# PTC_Thermistor_470R_VDiv.net
KiCad netlist of a schematic drawn in Altium Designer
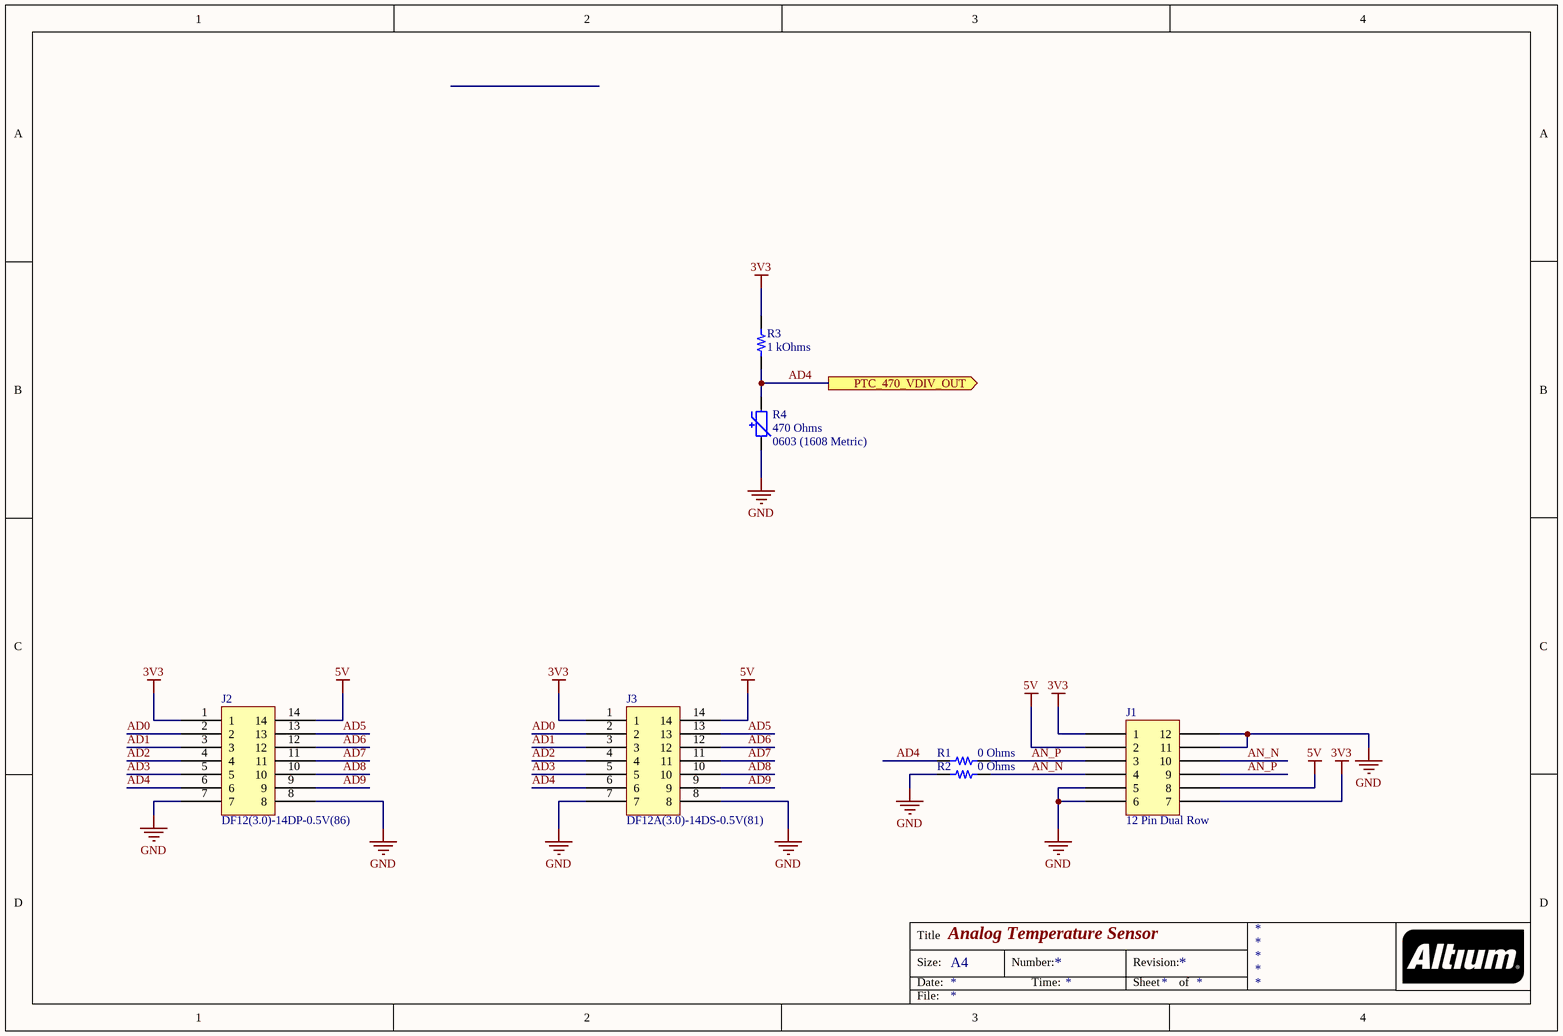
[diagram p0: PTC Thermistor 470R VDiv.SchDoc]

(export (version "E")
  (design (tool "Eeschema 10.0.6"))
  (components
    (comp (ref "J1")
      (value "12 Pin Dual Row")
      (footprint "TE 5650118-3 Card Edge")
      (libsource (lib "CelestialUseful") (part "12 Pin Dual Row"))
    )
    (comp (ref "J2")
      (value "DF12(3.0)-14DP-0.5V(86)")
      (footprint "HIROSE DF12 3.0-14DP-0.5V 86")
      (description "CONN HDR 14POS SMD GOLD")
      (fields (field (name "MANUFACTURER") "Hirose Electric Co Ltd"))
      (libsource (lib "altiumlibrary.com") (part "14 Pin Dual Row"))
    )
    (comp (ref "J3")
      (value "DF12A(3.0)-14DS-0.5V(81)")
      (footprint "HIROSE DF12A 3.0-14DS-0.5V 81")
      (description "CONN RCPT 14POS SMD GOLD")
      (fields (field (name "MANUFACTURER") "Hirose Electric Co Ltd"))
      (libsource (lib "altiumlibrary.com") (part "14 Pin Dual Row"))
    )
    (comp (ref "R1")
      (value "0 Ohms")
      (footprint "RES 0603_1608")
      (description "RES SMD 0 OHM JUMPER 1/10W 0603")
      (fields
        (field (name "PART NUMBER") "ERJ-3GEY0R00V")
        (field (name "MANUFACTURER") "Panasonic Electronic Components")
      )
      (libsource (lib "altiumlibrary.com") (part "Resistor"))
    )
    (comp (ref "R2")
      (value "0 Ohms")
      (footprint "RES 0603_1608")
      (description "RES SMD 0 OHM JUMPER 1/10W 0603")
      (fields
        (field (name "PART NUMBER") "ERJ-3GEY0R00V")
        (field (name "MANUFACTURER") "Panasonic Electronic Components")
      )
      (libsource (lib "altiumlibrary.com") (part "Resistor"))
    )
    (comp (ref "R3")
      (value "1 kOhms")
      (footprint "RES 0603_1608")
      (description "RES SMD 1K OHM 1% 1/10W 0603")
      (fields
        (field (name "PART NUMBER") "ERJ-3EKF1001V")
        (field (name "MANUFACTURER") "Panasonic Electronic Components")
      )
      (libsource (lib "altiumlibrary.com") (part "Resistor"))
    )
    (comp (ref "R4")
      (value "470 Ohms")
      (footprint "PTC 0603_1608")
      (description "THERMISTOR PTC 470 OHM 50% 0603")
      (fields
        (field (name "PART NUMBER") "PRF18BB471QB5RB")
        (field (name "MANUFACTURER") "Murata Electronics")
        (field (name "PACKAGE / CASE") "0603 (1608 Metric)")
      )
      (libsource (lib "altiumlibrary.com") (part "Thermistor PTC"))
    )
  )
  (nets
    (net (code "1") (name "/AD0") (class "Default")
      (node (ref "J2") (pin "2") (pinfunction "2_2") (pintype "passive"))
      (node (ref "J3") (pin "2") (pinfunction "2_2") (pintype "passive"))
    )
    (net (code "2") (name "/AD1") (class "Default")
      (node (ref "J2") (pin "3") (pinfunction "3_3") (pintype "passive"))
      (node (ref "J3") (pin "3") (pinfunction "3_3") (pintype "passive"))
    )
    (net (code "3") (name "/AD2") (class "Default")
      (node (ref "J2") (pin "4") (pinfunction "4_4") (pintype "passive"))
      (node (ref "J3") (pin "4") (pinfunction "4_4") (pintype "passive"))
    )
    (net (code "4") (name "/AD3") (class "Default")
      (node (ref "J2") (pin "5") (pinfunction "5_5") (pintype "passive"))
      (node (ref "J3") (pin "5") (pinfunction "5_5") (pintype "passive"))
    )
    (net (code "5") (name "/AD4") (class "Default")
      (node (ref "J2") (pin "6") (pinfunction "6_6") (pintype "passive"))
      (node (ref "J3") (pin "6") (pinfunction "6_6") (pintype "passive"))
      (node (ref "R1") (pin "1") (pinfunction "1_1") (pintype "passive"))
      (node (ref "R3") (pin "1") (pinfunction "1_1") (pintype "passive"))
      (node (ref "R4") (pin "1") (pinfunction "1_1") (pintype "passive"))
    )
    (net (code "6") (name "/AD5") (class "Default")
      (node (ref "J2") (pin "13") (pinfunction "13_13") (pintype "passive"))
      (node (ref "J3") (pin "13") (pinfunction "13_13") (pintype "passive"))
    )
    (net (code "7") (name "/AD6") (class "Default")
      (node (ref "J2") (pin "12") (pinfunction "12_12") (pintype "passive"))
      (node (ref "J3") (pin "12") (pinfunction "12_12") (pintype "passive"))
    )
    (net (code "8") (name "/AD7") (class "Default")
      (node (ref "J2") (pin "11") (pinfunction "11_11") (pintype "passive"))
      (node (ref "J3") (pin "11") (pinfunction "11_11") (pintype "passive"))
    )
    (net (code "9") (name "/AD8") (class "Default")
      (node (ref "J2") (pin "10") (pinfunction "10_10") (pintype "passive"))
      (node (ref "J3") (pin "10") (pinfunction "10_10") (pintype "passive"))
    )
    (net (code "10") (name "/AD9") (class "Default")
      (node (ref "J2") (pin "9") (pinfunction "9_9") (pintype "passive"))
      (node (ref "J3") (pin "9") (pinfunction "9_9") (pintype "passive"))
    )
    (net (code "11") (name "/AN_N") (class "Default")
      (node (ref "J1") (pin "10") (pinfunction "10_10") (pintype "passive"))
      (node (ref "J1") (pin "4") (pinfunction "4_4") (pintype "passive"))
      (node (ref "R2") (pin "2") (pinfunction "2_2") (pintype "passive"))
    )
    (net (code "12") (name "/AN_P") (class "Default")
      (node (ref "J1") (pin "3") (pinfunction "3_3") (pintype "passive"))
      (node (ref "J1") (pin "9") (pinfunction "9_9") (pintype "passive"))
      (node (ref "R1") (pin "2") (pinfunction "2_2") (pintype "passive"))
    )
    (net (code "13") (name "3V3") (class "Default")
      (node (ref "J1") (pin "1") (pinfunction "1_1") (pintype "passive"))
      (node (ref "J1") (pin "7") (pinfunction "7_7") (pintype "passive"))
      (node (ref "J2") (pin "1") (pinfunction "1_1") (pintype "passive"))
      (node (ref "J3") (pin "1") (pinfunction "1_1") (pintype "passive"))
      (node (ref "R3") (pin "2") (pinfunction "2_2") (pintype "passive"))
    )
    (net (code "14") (name "5V") (class "Default")
      (node (ref "J1") (pin "2") (pinfunction "2_2") (pintype "passive"))
      (node (ref "J1") (pin "8") (pinfunction "8_8") (pintype "passive"))
      (node (ref "J2") (pin "14") (pinfunction "14_14") (pintype "passive"))
      (node (ref "J3") (pin "14") (pinfunction "14_14") (pintype "passive"))
    )
    (net (code "15") (name "GND") (class "Default")
      (node (ref "J1") (pin "11") (pinfunction "11_11") (pintype "passive"))
      (node (ref "J1") (pin "12") (pinfunction "12_12") (pintype "passive"))
      (node (ref "J1") (pin "5") (pinfunction "5_5") (pintype "passive"))
      (node (ref "J1") (pin "6") (pinfunction "6_6") (pintype "passive"))
      (node (ref "J2") (pin "7") (pinfunction "7_7") (pintype "passive"))
      (node (ref "J2") (pin "8") (pinfunction "8_8") (pintype "passive"))
      (node (ref "J3") (pin "7") (pinfunction "7_7") (pintype "passive"))
      (node (ref "J3") (pin "8") (pinfunction "8_8") (pintype "passive"))
      (node (ref "R2") (pin "1") (pinfunction "1_1") (pintype "passive"))
      (node (ref "R4") (pin "2") (pinfunction "2_2") (pintype "passive"))
    )
  )
)
